# PCB.net
KiCad netlist of a schematic drawn in EAGLE
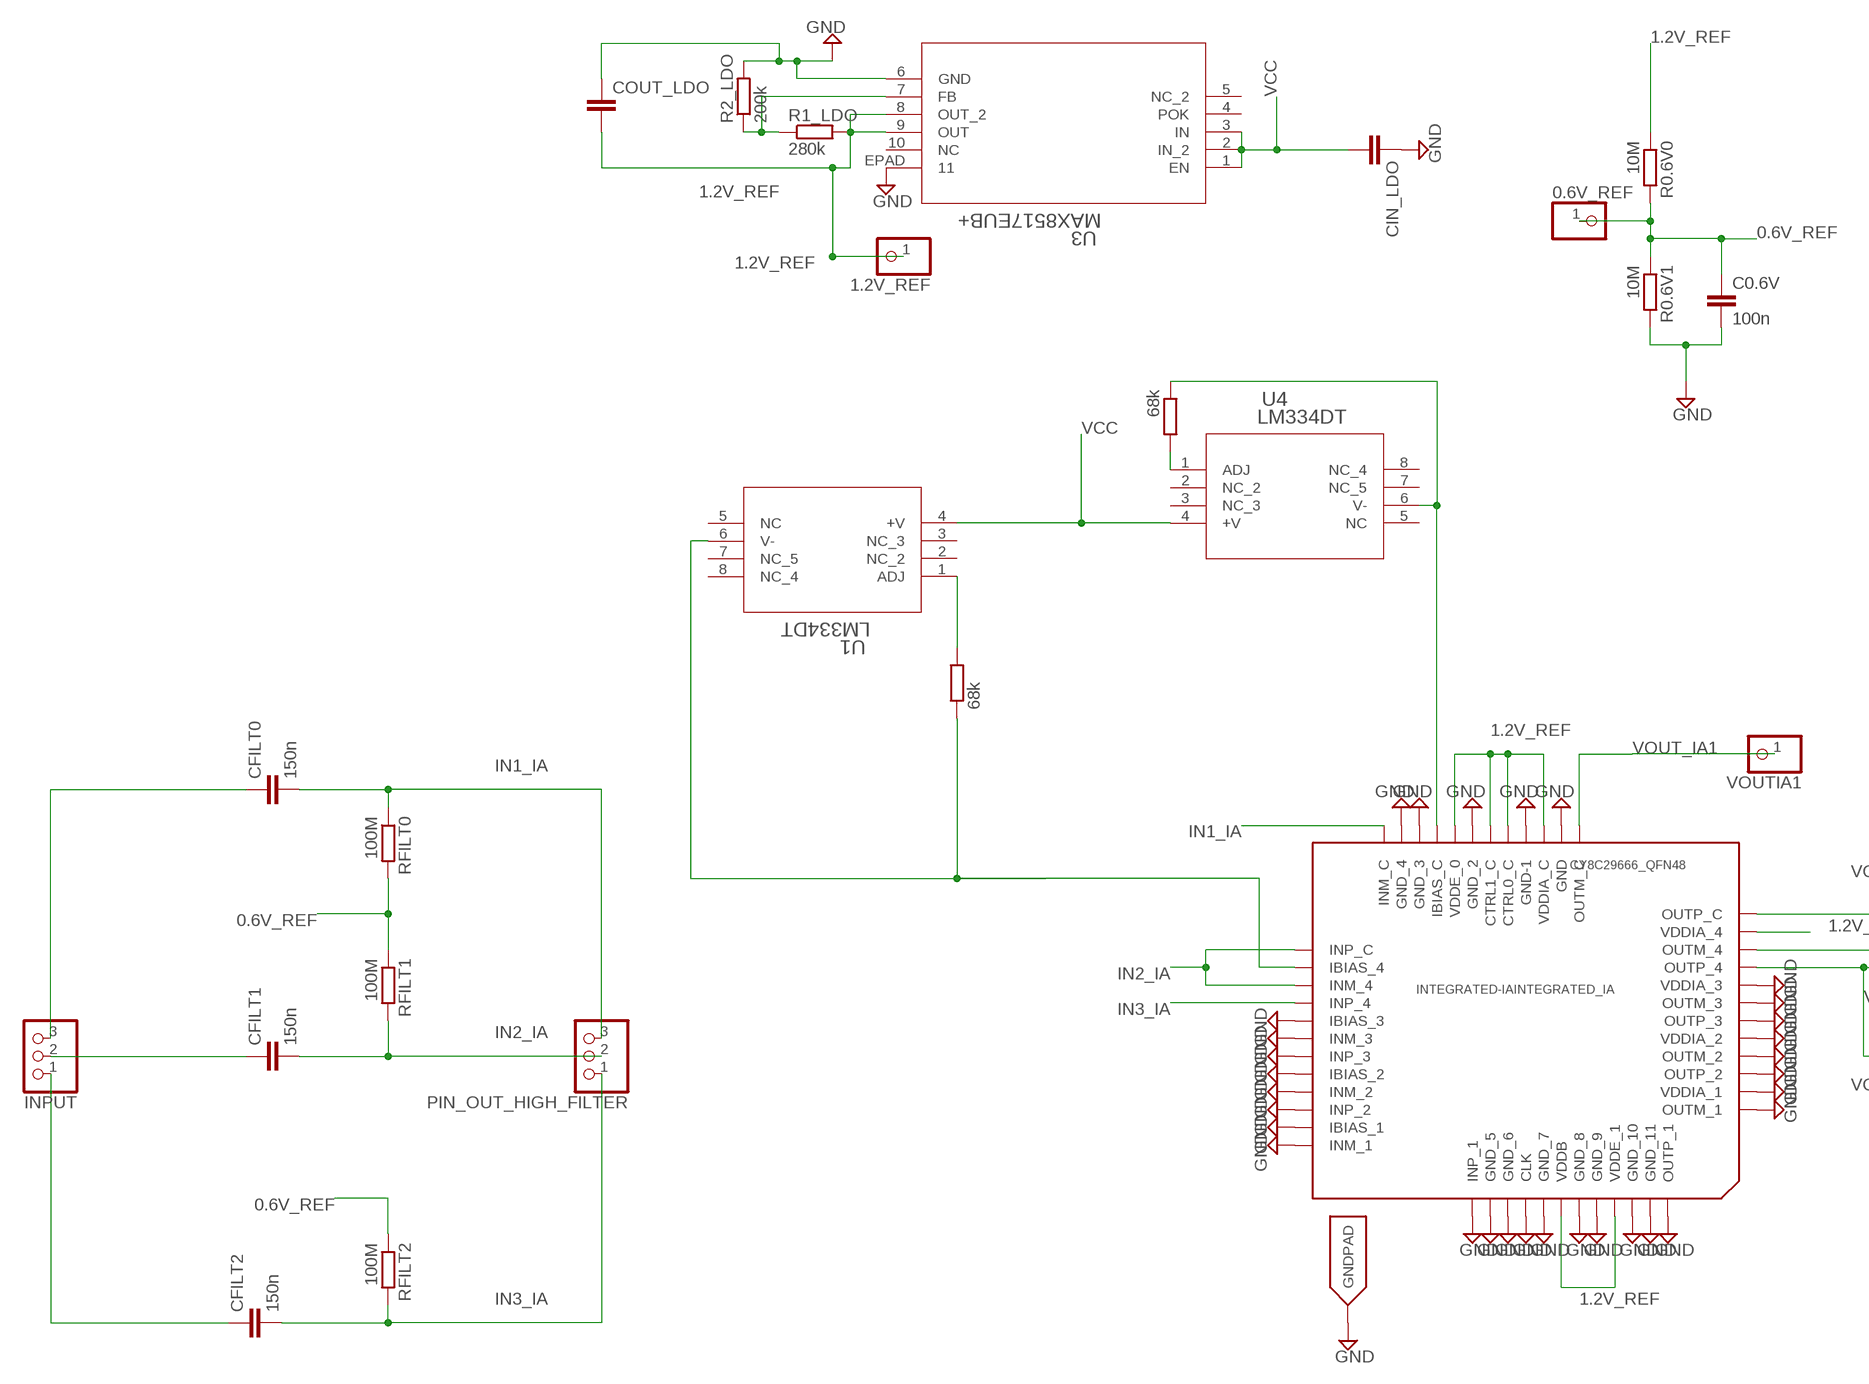
[diagram p0: schematic, sheet 1, part 1 of 2]
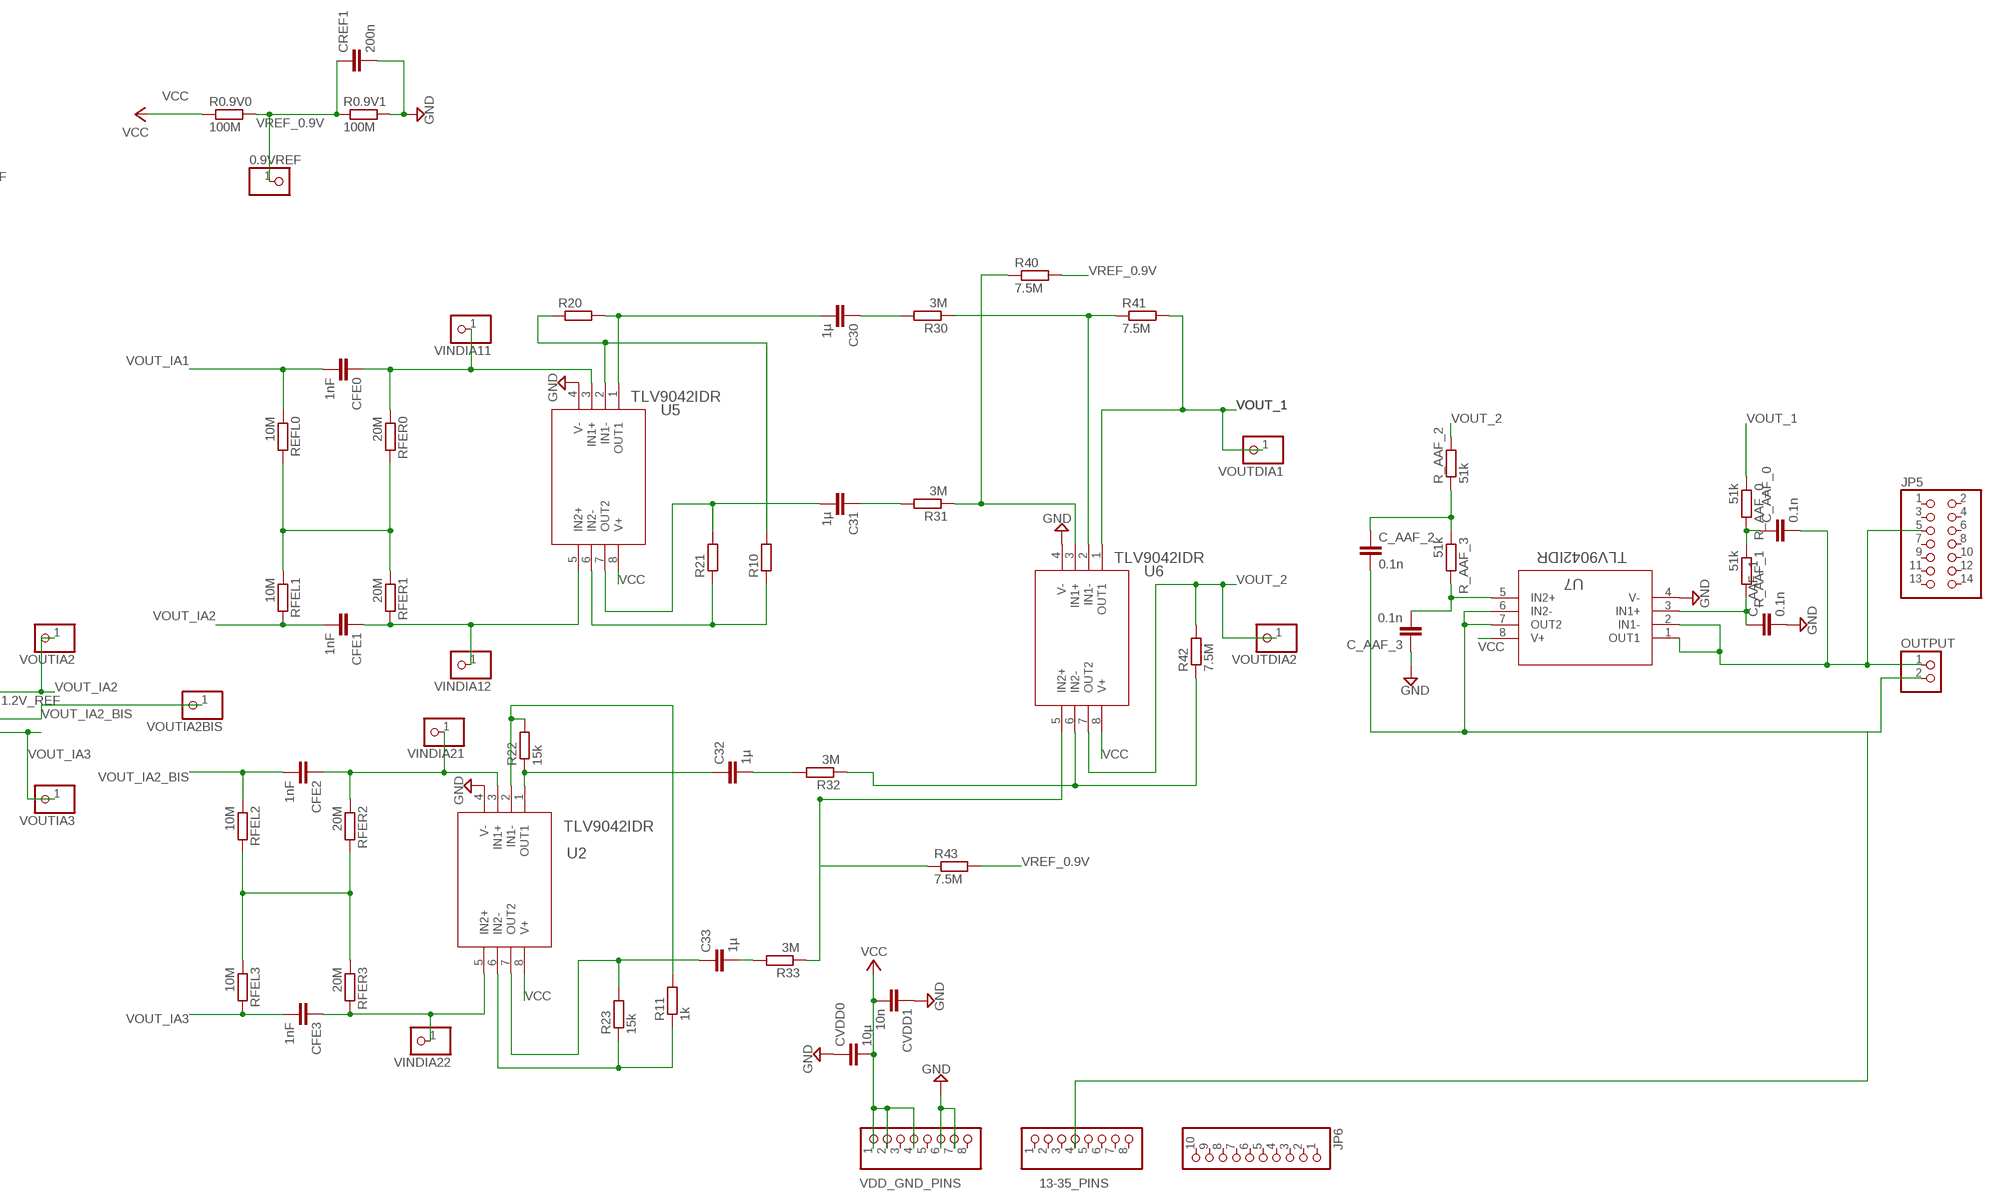
[diagram p1: schematic, sheet 1, part 2 of 2]

(export (version "E")
  (design (tool "Eeschema 10.0.6"))
  (components
    (comp (ref "0.6V_REF")
      (value "PINHD-1X1")
      (footprint "eagle-import:1X01")
      (libsource (lib "eagle-import") (part "PINHD-1X1"))
    )
    (comp (ref "0.9VREF")
      (value "PINHD-1X1")
      (footprint "eagle-import:1X01")
      (libsource (lib "eagle-import") (part "PINHD-1X1"))
    )
    (comp (ref "1.2V_REF")
      (value "PINHD-1X1")
      (footprint "eagle-import:1X01")
      (libsource (lib "eagle-import") (part "PINHD-1X1"))
    )
    (comp (ref "13-35_PINS")
      (value "PINHD-1X8")
      (footprint "eagle-import:1X08")
      (libsource (lib "eagle-import") (part "PINHD-1X8"))
    )
    (comp (ref "C0.6V")
      (value "100n")
      (footprint "eagle-import:C0603")
      (libsource (lib "eagle-import") (part "C-EUC0603"))
    )
    (comp (ref "C30")
      (value "1µ")
      (footprint "eagle-import:C0603")
      (libsource (lib "eagle-import") (part "C-EUC0603"))
    )
    (comp (ref "C31")
      (value "1µ")
      (footprint "eagle-import:C0603")
      (libsource (lib "eagle-import") (part "C-EUC0603"))
    )
    (comp (ref "C32")
      (value "1µ")
      (footprint "eagle-import:C0603")
      (libsource (lib "eagle-import") (part "C-EUC0603"))
    )
    (comp (ref "C33")
      (value "1µ")
      (footprint "eagle-import:C0603")
      (libsource (lib "eagle-import") (part "C-EUC0603"))
    )
    (comp (ref "CFE0")
      (value "1nF")
      (footprint "eagle-import:C0603")
      (libsource (lib "eagle-import") (part "C-EUC0603"))
    )
    (comp (ref "CFE1")
      (value "1nF")
      (footprint "eagle-import:C0603")
      (libsource (lib "eagle-import") (part "C-EUC0603"))
    )
    (comp (ref "CFE2")
      (value "1nF")
      (footprint "eagle-import:C0603")
      (libsource (lib "eagle-import") (part "C-EUC0603"))
    )
    (comp (ref "CFE3")
      (value "1nF")
      (footprint "eagle-import:C0603")
      (libsource (lib "eagle-import") (part "C-EUC0603"))
    )
    (comp (ref "CFILT0")
      (value "150n")
      (footprint "eagle-import:C0603")
      (libsource (lib "eagle-import") (part "C-EUC0603"))
    )
    (comp (ref "CFILT1")
      (value "150n")
      (footprint "eagle-import:C0603")
      (libsource (lib "eagle-import") (part "C-EUC0603"))
    )
    (comp (ref "CFILT2")
      (value "150n")
      (footprint "eagle-import:C0603")
      (libsource (lib "eagle-import") (part "C-EUC0603"))
    )
    (comp (ref "CIN_LDO")
      (value "1µ")
      (footprint "eagle-import:C0603")
      (libsource (lib "eagle-import") (part "C-EUC0603"))
    )
    (comp (ref "COUT_LDO")
      (value "4.7µ")
      (footprint "eagle-import:C0603")
      (libsource (lib "eagle-import") (part "C-EUC0603"))
    )
    (comp (ref "CREF1")
      (value "200n")
      (footprint "eagle-import:C0603")
      (libsource (lib "eagle-import") (part "C-EUC0603"))
    )
    (comp (ref "CVDD0")
      (value "10µ")
      (footprint "eagle-import:C0603")
      (libsource (lib "eagle-import") (part "C-EUC0603"))
    )
    (comp (ref "CVDD1")
      (value "10n")
      (footprint "eagle-import:C0603")
      (libsource (lib "eagle-import") (part "C-EUC0603"))
    )
    (comp (ref "C_AAF_0")
      (value "0.1n")
      (footprint "eagle-import:C0603")
      (libsource (lib "eagle-import") (part "C-EUC0603"))
    )
    (comp (ref "C_AAF_1")
      (value "0.1n")
      (footprint "eagle-import:C0603")
      (libsource (lib "eagle-import") (part "C-EUC0603"))
    )
    (comp (ref "C_AAF_2")
      (value "0.1n")
      (footprint "eagle-import:C0603")
      (libsource (lib "eagle-import") (part "C-EUC0603"))
    )
    (comp (ref "C_AAF_3")
      (value "0.1n")
      (footprint "eagle-import:C0603")
      (libsource (lib "eagle-import") (part "C-EUC0603"))
    )
    (comp (ref "INPUT")
      (value "PINHD-1X3")
      (footprint "eagle-import:1X03")
      (libsource (lib "eagle-import") (part "PINHD-1X3"))
    )
    (comp (ref "INTEGRATED-IA")
      (value "CY8C29666_QFN48")
      (footprint "eagle-import:QFN48")
      (libsource (lib "eagle-import") (part "CY8C29666_QFN48"))
    )
    (comp (ref "JP5")
      (value "PINHD-2X7")
      (footprint "eagle-import:2X07")
      (libsource (lib "eagle-import") (part "PINHD-2X7"))
    )
    (comp (ref "JP6")
      (value "PINHD-1X10")
      (footprint "eagle-import:1X10")
      (libsource (lib "eagle-import") (part "PINHD-1X10"))
    )
    (comp (ref "OUTPUT")
      (value "PINHD-1X2")
      (footprint "eagle-import:1X02")
      (libsource (lib "eagle-import") (part "PINHD-1X2"))
    )
    (comp (ref "PIN_OUT_HIGH_FILTER")
      (value "PINHD-1X3")
      (footprint "eagle-import:1X03")
      (libsource (lib "eagle-import") (part "PINHD-1X3"))
    )
    (comp (ref "R0.6V0")
      (value "10M")
      (footprint "eagle-import:R0603")
      (libsource (lib "eagle-import") (part "R-EU_R0603"))
    )
    (comp (ref "R0.6V1")
      (value "10M")
      (footprint "eagle-import:R0603")
      (libsource (lib "eagle-import") (part "R-EU_R0603"))
    )
    (comp (ref "R0.9V0")
      (value "100M")
      (footprint "eagle-import:R0603")
      (libsource (lib "eagle-import") (part "R-EU_R0603"))
    )
    (comp (ref "R0.9V1")
      (value "100M")
      (footprint "eagle-import:R0603")
      (libsource (lib "eagle-import") (part "R-EU_R0603"))
    )
    (comp (ref "R1_LDO")
      (value "280k")
      (footprint "eagle-import:R0603")
      (libsource (lib "eagle-import") (part "R-EU_R0603"))
    )
    (comp (ref "R2_LDO")
      (value "200k")
      (footprint "eagle-import:R0603")
      (libsource (lib "eagle-import") (part "R-EU_R0603"))
    )
    (comp (ref "R10")
      (value "R-EU_R0603")
      (footprint "eagle-import:R0603")
      (libsource (lib "eagle-import") (part "R-EU_R0603"))
    )
    (comp (ref "R11")
      (value "1k")
      (footprint "eagle-import:R0603")
      (libsource (lib "eagle-import") (part "R-EU_R0603"))
    )
    (comp (ref "R20")
      (value "R-EU_R0603")
      (footprint "eagle-import:R0603")
      (libsource (lib "eagle-import") (part "R-EU_R0603"))
    )
    (comp (ref "R21")
      (value "R-EU_R0603")
      (footprint "eagle-import:R0603")
      (libsource (lib "eagle-import") (part "R-EU_R0603"))
    )
    (comp (ref "R22")
      (value "15k")
      (footprint "eagle-import:R0603")
      (libsource (lib "eagle-import") (part "R-EU_R0603"))
    )
    (comp (ref "R23")
      (value "15k")
      (footprint "eagle-import:R0603")
      (libsource (lib "eagle-import") (part "R-EU_R0603"))
    )
    (comp (ref "R30")
      (value "3M")
      (footprint "eagle-import:R0603")
      (libsource (lib "eagle-import") (part "R-EU_R0603"))
    )
    (comp (ref "R31")
      (value "3M")
      (footprint "eagle-import:R0603")
      (libsource (lib "eagle-import") (part "R-EU_R0603"))
    )
    (comp (ref "R32")
      (value "3M")
      (footprint "eagle-import:R0603")
      (libsource (lib "eagle-import") (part "R-EU_R0603"))
    )
    (comp (ref "R33")
      (value "3M")
      (footprint "eagle-import:R0603")
      (libsource (lib "eagle-import") (part "R-EU_R0603"))
    )
    (comp (ref "R40")
      (value "7.5M")
      (footprint "eagle-import:R0603")
      (libsource (lib "eagle-import") (part "R-EU_R0603"))
    )
    (comp (ref "R41")
      (value "7.5M")
      (footprint "eagle-import:R0603")
      (libsource (lib "eagle-import") (part "R-EU_R0603"))
    )
    (comp (ref "R42")
      (value "7.5M")
      (footprint "eagle-import:R0603")
      (libsource (lib "eagle-import") (part "R-EU_R0603"))
    )
    (comp (ref "R43")
      (value "7.5M")
      (footprint "eagle-import:R0603")
      (libsource (lib "eagle-import") (part "R-EU_R0603"))
    )
    (comp (ref "REFL0")
      (value "10M")
      (footprint "eagle-import:R0603")
      (libsource (lib "eagle-import") (part "R-EU_R0603"))
    )
    (comp (ref "RFEL1")
      (value "10M")
      (footprint "eagle-import:R0603")
      (libsource (lib "eagle-import") (part "R-EU_R0603"))
    )
    (comp (ref "RFEL2")
      (value "10M")
      (footprint "eagle-import:R0603")
      (libsource (lib "eagle-import") (part "R-EU_R0603"))
    )
    (comp (ref "RFEL3")
      (value "10M")
      (footprint "eagle-import:R0603")
      (libsource (lib "eagle-import") (part "R-EU_R0603"))
    )
    (comp (ref "RFER0")
      (value "20M")
      (footprint "eagle-import:R0603")
      (libsource (lib "eagle-import") (part "R-EU_R0603"))
    )
    (comp (ref "RFER1")
      (value "20M")
      (footprint "eagle-import:R0603")
      (libsource (lib "eagle-import") (part "R-EU_R0603"))
    )
    (comp (ref "RFER2")
      (value "20M")
      (footprint "eagle-import:R0603")
      (libsource (lib "eagle-import") (part "R-EU_R0603"))
    )
    (comp (ref "RFER3")
      (value "20M")
      (footprint "eagle-import:R0603")
      (libsource (lib "eagle-import") (part "R-EU_R0603"))
    )
    (comp (ref "RFILT0")
      (value "100M")
      (footprint "eagle-import:R0603")
      (libsource (lib "eagle-import") (part "R-EU_R0603"))
    )
    (comp (ref "RFILT1")
      (value "100M")
      (footprint "eagle-import:R0603")
      (libsource (lib "eagle-import") (part "R-EU_R0603"))
    )
    (comp (ref "RFILT2")
      (value "100M")
      (footprint "eagle-import:R0603")
      (libsource (lib "eagle-import") (part "R-EU_R0603"))
    )
    (comp (ref "RLM334_0")
      (value "68k")
      (footprint "eagle-import:R0603")
      (libsource (lib "eagle-import") (part "R-EU_R0603"))
    )
    (comp (ref "RLM334_1")
      (value "68k")
      (footprint "eagle-import:R0603")
      (libsource (lib "eagle-import") (part "R-EU_R0603"))
    )
    (comp (ref "R_AAF_0")
      (value "51k")
      (footprint "eagle-import:R0603")
      (libsource (lib "eagle-import") (part "R-EU_R0603"))
    )
    (comp (ref "R_AAF_1")
      (value "51k")
      (footprint "eagle-import:R0603")
      (libsource (lib "eagle-import") (part "R-EU_R0603"))
    )
    (comp (ref "R_AAF_2")
      (value "51k")
      (footprint "eagle-import:R0603")
      (libsource (lib "eagle-import") (part "R-EU_R0603"))
    )
    (comp (ref "R_AAF_3")
      (value "51k")
      (footprint "eagle-import:R0603")
      (libsource (lib "eagle-import") (part "R-EU_R0603"))
    )
    (comp (ref "U1")
      (value "LM334DT")
      (footprint "eagle-import:SO-8_STM")
      (libsource (lib "eagle-import") (part "LM334DT"))
    )
    (comp (ref "U2")
      (value "TLV9042IDR")
      (footprint "eagle-import:SOIC8_D_TEX")
      (fields (field (name "COPYRIGHT") "Copyright (C) 2018 Accelerated Designs. All rights reserved"))
      (libsource (lib "eagle-import") (part "TLV9042IDR"))
    )
    (comp (ref "U3")
      (value "MAX8517EUB+")
      (footprint "eagle-import:21-0109D_MXM")
      (libsource (lib "eagle-import") (part "MAX8517EUB+"))
    )
    (comp (ref "U4")
      (value "LM334DT")
      (footprint "eagle-import:SO-8_STM")
      (libsource (lib "eagle-import") (part "LM334DT"))
    )
    (comp (ref "U5")
      (value "TLV9042IDR")
      (footprint "eagle-import:SOIC8_D_TEX")
      (fields (field (name "COPYRIGHT") "Copyright (C) 2018 Accelerated Designs. All rights reserved"))
      (libsource (lib "eagle-import") (part "TLV9042IDR"))
    )
    (comp (ref "U6")
      (value "TLV9042IDR")
      (footprint "eagle-import:SOIC8_D_TEX")
      (fields (field (name "COPYRIGHT") "Copyright (C) 2018 Accelerated Designs. All rights reserved"))
      (libsource (lib "eagle-import") (part "TLV9042IDR"))
    )
    (comp (ref "U7")
      (value "TLV9042IDR")
      (footprint "eagle-import:SOIC8_D_TEX")
      (fields (field (name "COPYRIGHT") "Copyright (C) 2018 Accelerated Designs. All rights reserved"))
      (libsource (lib "eagle-import") (part "TLV9042IDR"))
    )
    (comp (ref "VDD_GND_PINS")
      (value "PINHD-1X8")
      (footprint "eagle-import:1X08")
      (libsource (lib "eagle-import") (part "PINHD-1X8"))
    )
    (comp (ref "VINDIA11")
      (value "PINHD-1X1")
      (footprint "eagle-import:1X01")
      (libsource (lib "eagle-import") (part "PINHD-1X1"))
    )
    (comp (ref "VINDIA12")
      (value "PINHD-1X1")
      (footprint "eagle-import:1X01")
      (libsource (lib "eagle-import") (part "PINHD-1X1"))
    )
    (comp (ref "VINDIA21")
      (value "PINHD-1X1")
      (footprint "eagle-import:1X01")
      (libsource (lib "eagle-import") (part "PINHD-1X1"))
    )
    (comp (ref "VINDIA22")
      (value "PINHD-1X1")
      (footprint "eagle-import:1X01")
      (libsource (lib "eagle-import") (part "PINHD-1X1"))
    )
    (comp (ref "VOUTDIA1")
      (value "PINHD-1X1")
      (footprint "eagle-import:1X01")
      (libsource (lib "eagle-import") (part "PINHD-1X1"))
    )
    (comp (ref "VOUTDIA2")
      (value "PINHD-1X1")
      (footprint "eagle-import:1X01")
      (libsource (lib "eagle-import") (part "PINHD-1X1"))
    )
    (comp (ref "VOUTIA1")
      (value "PINHD-1X1")
      (footprint "eagle-import:1X01")
      (libsource (lib "eagle-import") (part "PINHD-1X1"))
    )
    (comp (ref "VOUTIA2")
      (value "PINHD-1X1")
      (footprint "eagle-import:1X01")
      (libsource (lib "eagle-import") (part "PINHD-1X1"))
    )
    (comp (ref "VOUTIA2BIS")
      (value "PINHD-1X1")
      (footprint "eagle-import:1X01")
      (libsource (lib "eagle-import") (part "PINHD-1X1"))
    )
    (comp (ref "VOUTIA3")
      (value "PINHD-1X1")
      (footprint "eagle-import:1X01")
      (libsource (lib "eagle-import") (part "PINHD-1X1"))
    )
  )
  (nets
    (net (code "1") (name "/0.6V_REF") (class "Default")
      (node (ref "0.6V_REF") (pin "1") (pinfunction "1_1") (pintype "passive"))
      (node (ref "C0.6V") (pin "1") (pinfunction "1_1") (pintype "passive"))
      (node (ref "R0.6V0") (pin "2") (pinfunction "2_2") (pintype "passive"))
      (node (ref "R0.6V1") (pin "1") (pinfunction "1_1") (pintype "passive"))
      (node (ref "RFILT0") (pin "2") (pinfunction "2_2") (pintype "passive"))
      (node (ref "RFILT1") (pin "1") (pinfunction "1_1") (pintype "passive"))
      (node (ref "RFILT2") (pin "1") (pinfunction "1_1") (pintype "passive"))
    )
    (net (code "2") (name "/1.2V_REF") (class "Default")
      (node (ref "1.2V_REF") (pin "1") (pinfunction "1_1") (pintype "passive"))
      (node (ref "COUT_LDO") (pin "2") (pinfunction "2_2") (pintype "passive"))
      (node (ref "INTEGRATED-IA") (pin "11") (pinfunction "VDDIA_4_11") (pintype "bidirectional"))
      (node (ref "INTEGRATED-IA") (pin "15") (pinfunction "VDDIA_C_15") (pintype "bidirectional"))
      (node (ref "INTEGRATED-IA") (pin "17") (pinfunction "CTRL0_C_17") (pintype "bidirectional"))
      (node (ref "INTEGRATED-IA") (pin "18") (pinfunction "CTRL1_C_18") (pintype "power_in"))
      (node (ref "INTEGRATED-IA") (pin "20") (pinfunction "VDDE_0_20") (pintype "bidirectional"))
      (node (ref "INTEGRATED-IA") (pin "42") (pinfunction "VDDB_42") (pintype "power_in"))
      (node (ref "INTEGRATED-IA") (pin "45") (pinfunction "VDDE_1_45") (pintype "bidirectional"))
      (node (ref "R0.6V0") (pin "1") (pinfunction "1_1") (pintype "passive"))
      (node (ref "R1_LDO") (pin "2") (pinfunction "2_2") (pintype "passive"))
      (node (ref "U3") (pin "8") (pinfunction "OUT_2_8") (pintype "output"))
      (node (ref "U3") (pin "9") (pinfunction "OUT_9") (pintype "output"))
    )
    (net (code "3") (name "/IN1_IA") (class "Default")
      (node (ref "CFILT0") (pin "2") (pinfunction "2_2") (pintype "passive"))
      (node (ref "INTEGRATED-IA") (pin "24") (pinfunction "INM_C_24") (pintype "bidirectional"))
      (node (ref "PIN_OUT_HIGH_FILTER") (pin "3") (pinfunction "3_3") (pintype "passive"))
      (node (ref "RFILT0") (pin "1") (pinfunction "1_1") (pintype "passive"))
    )
    (net (code "4") (name "/IN2_IA") (class "Default")
      (node (ref "CFILT1") (pin "2") (pinfunction "2_2") (pintype "passive"))
      (node (ref "INTEGRATED-IA") (pin "25") (pinfunction "INP_C_25") (pintype "bidirectional"))
      (node (ref "INTEGRATED-IA") (pin "27") (pinfunction "INM_4_27") (pintype "bidirectional"))
      (node (ref "PIN_OUT_HIGH_FILTER") (pin "2") (pinfunction "2_2") (pintype "passive"))
      (node (ref "RFILT1") (pin "2") (pinfunction "2_2") (pintype "passive"))
    )
    (net (code "5") (name "/IN3_IA") (class "Default")
      (node (ref "CFILT2") (pin "2") (pinfunction "2_2") (pintype "passive"))
      (node (ref "INTEGRATED-IA") (pin "28") (pinfunction "INP_4_28") (pintype "bidirectional"))
      (node (ref "PIN_OUT_HIGH_FILTER") (pin "1") (pinfunction "1_1") (pintype "passive"))
      (node (ref "RFILT2") (pin "2") (pinfunction "2_2") (pintype "passive"))
    )
    (net (code "6") (name "/VOUT_1") (class "Default")
      (node (ref "R41") (pin "2") (pinfunction "2_2") (pintype "passive"))
      (node (ref "R_AAF_0") (pin "1") (pinfunction "1_1") (pintype "passive"))
      (node (ref "U6") (pin "1") (pinfunction "OUT1_1") (pintype "output"))
      (node (ref "VOUTDIA1") (pin "1") (pinfunction "1_1") (pintype "passive"))
    )
    (net (code "7") (name "/VOUT_2") (class "Default")
      (node (ref "R42") (pin "2") (pinfunction "2_2") (pintype "passive"))
      (node (ref "R_AAF_2") (pin "2") (pinfunction "2_2") (pintype "passive"))
      (node (ref "U6") (pin "7") (pinfunction "OUT2_7") (pintype "output"))
      (node (ref "VOUTDIA2") (pin "1") (pinfunction "1_1") (pintype "passive"))
    )
    (net (code "8") (name "/VOUT_IA1") (class "Default")
      (node (ref "CFE0") (pin "2") (pinfunction "2_2") (pintype "passive"))
      (node (ref "INTEGRATED-IA") (pin "13") (pinfunction "OUTM_C_13") (pintype "bidirectional"))
      (node (ref "REFL0") (pin "1") (pinfunction "1_1") (pintype "passive"))
      (node (ref "VOUTIA1") (pin "1") (pinfunction "1_1") (pintype "passive"))
    )
    (net (code "9") (name "/VOUT_IA2") (class "Default")
      (node (ref "CFE1") (pin "2") (pinfunction "2_2") (pintype "passive"))
      (node (ref "INTEGRATED-IA") (pin "12") (pinfunction "OUTP_C_12") (pintype "bidirectional"))
      (node (ref "RFEL1") (pin "2") (pinfunction "2_2") (pintype "passive"))
      (node (ref "VOUTIA2") (pin "1") (pinfunction "1_1") (pintype "passive"))
    )
    (net (code "10") (name "/VOUT_IA2_BIS") (class "Default")
      (node (ref "CFE2") (pin "2") (pinfunction "2_2") (pintype "passive"))
      (node (ref "INTEGRATED-IA") (pin "10") (pinfunction "OUTM_4_10") (pintype "bidirectional"))
      (node (ref "RFEL2") (pin "1") (pinfunction "1_1") (pintype "passive"))
      (node (ref "VOUTIA2BIS") (pin "1") (pinfunction "1_1") (pintype "passive"))
    )
    (net (code "11") (name "/VOUT_IA3") (class "Default")
      (node (ref "CFE3") (pin "2") (pinfunction "2_2") (pintype "passive"))
      (node (ref "INTEGRATED-IA") (pin "9") (pinfunction "OUTP_4_9") (pintype "bidirectional"))
      (node (ref "RFEL3") (pin "2") (pinfunction "2_2") (pintype "passive"))
      (node (ref "VOUTIA3") (pin "1") (pinfunction "1_1") (pintype "passive"))
    )
    (net (code "12") (name "/VREF_0.9V") (class "Default")
      (node (ref "0.9VREF") (pin "1") (pinfunction "1_1") (pintype "passive"))
      (node (ref "CREF1") (pin "1") (pinfunction "1_1") (pintype "passive"))
      (node (ref "R0.9V0") (pin "2") (pinfunction "2_2") (pintype "passive"))
      (node (ref "R0.9V1") (pin "1") (pinfunction "1_1") (pintype "passive"))
      (node (ref "R40") (pin "2") (pinfunction "2_2") (pintype "passive"))
      (node (ref "R43") (pin "2") (pinfunction "2_2") (pintype "passive"))
    )
    (net (code "13") (name "GND") (class "Default")
      (node (ref "C0.6V") (pin "2") (pinfunction "2_2") (pintype "passive"))
      (node (ref "CIN_LDO") (pin "1") (pinfunction "1_1") (pintype "passive"))
      (node (ref "COUT_LDO") (pin "1") (pinfunction "1_1") (pintype "passive"))
      (node (ref "CREF1") (pin "2") (pinfunction "2_2") (pintype "passive"))
      (node (ref "CVDD0") (pin "1") (pinfunction "1_1") (pintype "passive"))
      (node (ref "CVDD1") (pin "1") (pinfunction "1_1") (pintype "passive"))
      (node (ref "C_AAF_1") (pin "2") (pinfunction "2_2") (pintype "passive"))
      (node (ref "C_AAF_3") (pin "1") (pinfunction "1_1") (pintype "passive"))
      (node (ref "INTEGRATED-IA") (pin "1") (pinfunction "OUTM_1_1") (pintype "bidirectional"))
      (node (ref "INTEGRATED-IA") (pin "14") (pinfunction "GND_14") (pintype "bidirectional"))
      (node (ref "INTEGRATED-IA") (pin "16") (pinfunction "GND-1_16") (pintype "bidirectional"))
      (node (ref "INTEGRATED-IA") (pin "19") (pinfunction "GND_2_19") (pintype "bidirectional"))
      (node (ref "INTEGRATED-IA") (pin "2") (pinfunction "VDDIA_1_2") (pintype "bidirectional"))
      (node (ref "INTEGRATED-IA") (pin "22") (pinfunction "GND_3_22") (pintype "bidirectional"))
      (node (ref "INTEGRATED-IA") (pin "23") (pinfunction "GND_4_23") (pintype "bidirectional"))
      (node (ref "INTEGRATED-IA") (pin "29") (pinfunction "IBIAS_3_29") (pintype "bidirectional"))
      (node (ref "INTEGRATED-IA") (pin "3") (pinfunction "OUTP_2_3") (pintype "bidirectional"))
      (node (ref "INTEGRATED-IA") (pin "30") (pinfunction "INM_3_30") (pintype "bidirectional"))
      (node (ref "INTEGRATED-IA") (pin "31") (pinfunction "INP_3_31") (pintype "bidirectional"))
      (node (ref "INTEGRATED-IA") (pin "32") (pinfunction "IBIAS_2_32") (pintype "bidirectional"))
      (node (ref "INTEGRATED-IA") (pin "33") (pinfunction "INM_2_33") (pintype "bidirectional"))
      (node (ref "INTEGRATED-IA") (pin "34") (pinfunction "INP_2_34") (pintype "bidirectional"))
      (node (ref "INTEGRATED-IA") (pin "35") (pinfunction "IBIAS_1_35") (pintype "bidirectional"))
      (node (ref "INTEGRATED-IA") (pin "36") (pinfunction "INM_1_36") (pintype "bidirectional"))
      (node (ref "INTEGRATED-IA") (pin "37") (pinfunction "INP_1_37") (pintype "bidirectional"))
      (node (ref "INTEGRATED-IA") (pin "38") (pinfunction "GND_5_38") (pintype "bidirectional"))
      (node (ref "INTEGRATED-IA") (pin "39") (pinfunction "GND_6_39") (pintype "bidirectional"))
      (node (ref "INTEGRATED-IA") (pin "4") (pinfunction "OUTM_2_4") (pintype "bidirectional"))
      (node (ref "INTEGRATED-IA") (pin "40") (pinfunction "CLK_40") (pintype "bidirectional"))
      (node (ref "INTEGRATED-IA") (pin "41") (pinfunction "GND_7_41") (pintype "bidirectional"))
      (node (ref "INTEGRATED-IA") (pin "43") (pinfunction "GND_8_43") (pintype "bidirectional"))
      (node (ref "INTEGRATED-IA") (pin "44") (pinfunction "GND_9_44") (pintype "bidirectional"))
      (node (ref "INTEGRATED-IA") (pin "46") (pinfunction "GND_10_46") (pintype "bidirectional"))
      (node (ref "INTEGRATED-IA") (pin "47") (pinfunction "GND_11_47") (pintype "bidirectional"))
      (node (ref "INTEGRATED-IA") (pin "48") (pinfunction "OUTP_1_48") (pintype "bidirectional"))
      (node (ref "INTEGRATED-IA") (pin "5") (pinfunction "VDDIA_2_5") (pintype "bidirectional"))
      (node (ref "INTEGRATED-IA") (pin "6") (pinfunction "OUTP_3_6") (pintype "bidirectional"))
      (node (ref "INTEGRATED-IA") (pin "7") (pinfunction "OUTM_3_7") (pintype "power_in"))
      (node (ref "INTEGRATED-IA") (pin "8") (pinfunction "VDDIA_3_8") (pintype "bidirectional"))
      (node (ref "INTEGRATED-IA") (pin "EXP") (pinfunction "GNDPAD_EXP") (pintype "power_in"))
      (node (ref "R0.6V1") (pin "2") (pinfunction "2_2") (pintype "passive"))
      (node (ref "R0.9V1") (pin "2") (pinfunction "2_2") (pintype "passive"))
      (node (ref "R2_LDO") (pin "2") (pinfunction "2_2") (pintype "passive"))
      (node (ref "U2") (pin "4") (pinfunction "V-_4") (pintype "power_in"))
      (node (ref "U3") (pin "6") (pinfunction "GND_6") (pintype "power_in"))
      (node (ref "U3") (pin "EPAD") (pinfunction "11_EPAD") (pintype "passive"))
      (node (ref "U5") (pin "4") (pinfunction "V-_4") (pintype "power_in"))
      (node (ref "U6") (pin "4") (pinfunction "V-_4") (pintype "power_in"))
      (node (ref "U7") (pin "4") (pinfunction "V-_4") (pintype "power_in"))
      (node (ref "VDD_GND_PINS") (pin "6") (pinfunction "6_6") (pintype "passive"))
      (node (ref "VDD_GND_PINS") (pin "7") (pinfunction "7_7") (pintype "passive"))
    )
    (net (code "14") (name "Net-(C30-Pad1)") (class "Default")
      (node (ref "C30") (pin "1") (pinfunction "1_1") (pintype "passive"))
      (node (ref "R30") (pin "2") (pinfunction "2_2") (pintype "passive"))
    )
    (net (code "15") (name "Net-(C31-Pad1)") (class "Default")
      (node (ref "C31") (pin "1") (pinfunction "1_1") (pintype "passive"))
      (node (ref "R31") (pin "2") (pinfunction "2_2") (pintype "passive"))
    )
    (net (code "16") (name "Net-(C32-Pad2)") (class "Default")
      (node (ref "C32") (pin "2") (pinfunction "2_2") (pintype "passive"))
      (node (ref "R32") (pin "2") (pinfunction "2_2") (pintype "passive"))
    )
    (net (code "17") (name "Net-(C33-Pad2)") (class "Default")
      (node (ref "C33") (pin "2") (pinfunction "2_2") (pintype "passive"))
      (node (ref "R33") (pin "2") (pinfunction "2_2") (pintype "passive"))
    )
    (net (code "18") (name "Net-(CFILT0-Pad1)") (class "Default")
      (node (ref "CFILT0") (pin "1") (pinfunction "1_1") (pintype "passive"))
      (node (ref "INPUT") (pin "3") (pinfunction "3_3") (pintype "passive"))
    )
    (net (code "19") (name "Net-(CFILT1-Pad1)") (class "Default")
      (node (ref "CFILT1") (pin "1") (pinfunction "1_1") (pintype "passive"))
      (node (ref "INPUT") (pin "2") (pinfunction "2_2") (pintype "passive"))
    )
    (net (code "20") (name "Net-(CFILT2-Pad1)") (class "Default")
      (node (ref "CFILT2") (pin "1") (pinfunction "1_1") (pintype "passive"))
      (node (ref "INPUT") (pin "1") (pinfunction "1_1") (pintype "passive"))
    )
    (net (code "21") (name "Net-(C_AAF_0-Pad1)") (class "Default")
      (node (ref "C_AAF_0") (pin "1") (pinfunction "1_1") (pintype "passive"))
      (node (ref "R_AAF_0") (pin "2") (pinfunction "2_2") (pintype "passive"))
      (node (ref "R_AAF_1") (pin "1") (pinfunction "1_1") (pintype "passive"))
    )
    (net (code "22") (name "Net-(C_AAF_2-Pad1)") (class "Default")
      (node (ref "C_AAF_2") (pin "1") (pinfunction "1_1") (pintype "passive"))
      (node (ref "R_AAF_2") (pin "1") (pinfunction "1_1") (pintype "passive"))
      (node (ref "R_AAF_3") (pin "1") (pinfunction "1_1") (pintype "passive"))
    )
    (net (code "23") (name "Net-(INTEGRATED-IAB-IBIAS_4)") (class "Default")
      (node (ref "INTEGRATED-IA") (pin "26") (pinfunction "IBIAS_4_26") (pintype "bidirectional"))
      (node (ref "RLM334_1") (pin "1") (pinfunction "1_1") (pintype "passive"))
      (node (ref "U1") (pin "6") (pinfunction "V-_6") (pintype "power_in"))
    )
    (net (code "24") (name "Net-(INTEGRATED-IAB-IBIAS_C)") (class "Default")
      (node (ref "INTEGRATED-IA") (pin "21") (pinfunction "IBIAS_C_21") (pintype "bidirectional"))
      (node (ref "RLM334_0") (pin "1") (pinfunction "1_1") (pintype "passive"))
      (node (ref "U4") (pin "6") (pinfunction "V-_6") (pintype "power_in"))
    )
    (net (code "25") (name "Net-(REFL0-Pad2)") (class "Default")
      (node (ref "REFL0") (pin "2") (pinfunction "2_2") (pintype "passive"))
      (node (ref "RFEL1") (pin "1") (pinfunction "1_1") (pintype "passive"))
      (node (ref "RFER0") (pin "2") (pinfunction "2_2") (pintype "passive"))
      (node (ref "RFER1") (pin "1") (pinfunction "1_1") (pintype "passive"))
    )
    (net (code "26") (name "Net-(RFEL2-Pad2)") (class "Default")
      (node (ref "RFEL2") (pin "2") (pinfunction "2_2") (pintype "passive"))
      (node (ref "RFEL3") (pin "1") (pinfunction "1_1") (pintype "passive"))
      (node (ref "RFER2") (pin "2") (pinfunction "2_2") (pintype "passive"))
      (node (ref "RFER3") (pin "1") (pinfunction "1_1") (pintype "passive"))
    )
    (net (code "27") (name "Net-(U1-ADJ)") (class "Default")
      (node (ref "RLM334_1") (pin "2") (pinfunction "2_2") (pintype "passive"))
      (node (ref "U1") (pin "1") (pinfunction "ADJ_1") (pintype "input"))
    )
    (net (code "28") (name "Net-(U2-IN1+)") (class "Default")
      (node (ref "CFE2") (pin "1") (pinfunction "1_1") (pintype "passive"))
      (node (ref "RFER2") (pin "1") (pinfunction "1_1") (pintype "passive"))
      (node (ref "U2") (pin "3") (pinfunction "IN1+_3") (pintype "input"))
      (node (ref "VINDIA21") (pin "1") (pinfunction "1_1") (pintype "passive"))
    )
    (net (code "29") (name "Net-(U2-IN1-)") (class "Default")
      (node (ref "R11") (pin "2") (pinfunction "2_2") (pintype "passive"))
      (node (ref "R22") (pin "2") (pinfunction "2_2") (pintype "passive"))
      (node (ref "U2") (pin "2") (pinfunction "IN1-_2") (pintype "input"))
    )
    (net (code "30") (name "Net-(U2-IN2+)") (class "Default")
      (node (ref "CFE3") (pin "1") (pinfunction "1_1") (pintype "passive"))
      (node (ref "RFER3") (pin "2") (pinfunction "2_2") (pintype "passive"))
      (node (ref "U2") (pin "5") (pinfunction "IN2+_5") (pintype "input"))
      (node (ref "VINDIA22") (pin "1") (pinfunction "1_1") (pintype "passive"))
    )
    (net (code "31") (name "Net-(U2-IN2-)") (class "Default")
      (node (ref "R11") (pin "1") (pinfunction "1_1") (pintype "passive"))
      (node (ref "R23") (pin "1") (pinfunction "1_1") (pintype "passive"))
      (node (ref "U2") (pin "6") (pinfunction "IN2-_6") (pintype "input"))
    )
    (net (code "32") (name "Net-(U2-OUT1)") (class "Default")
      (node (ref "C32") (pin "1") (pinfunction "1_1") (pintype "passive"))
      (node (ref "R22") (pin "1") (pinfunction "1_1") (pintype "passive"))
      (node (ref "U2") (pin "1") (pinfunction "OUT1_1") (pintype "output"))
    )
    (net (code "33") (name "Net-(U2-OUT2)") (class "Default")
      (node (ref "C33") (pin "1") (pinfunction "1_1") (pintype "passive"))
      (node (ref "R23") (pin "2") (pinfunction "2_2") (pintype "passive"))
      (node (ref "U2") (pin "7") (pinfunction "OUT2_7") (pintype "output"))
    )
    (net (code "34") (name "Net-(U3-FB)") (class "Default")
      (node (ref "R1_LDO") (pin "1") (pinfunction "1_1") (pintype "passive"))
      (node (ref "R2_LDO") (pin "1") (pinfunction "1_1") (pintype "passive"))
      (node (ref "U3") (pin "7") (pinfunction "FB_7") (pintype "passive"))
    )
    (net (code "35") (name "Net-(U4-ADJ)") (class "Default")
      (node (ref "RLM334_0") (pin "2") (pinfunction "2_2") (pintype "passive"))
      (node (ref "U4") (pin "1") (pinfunction "ADJ_1") (pintype "input"))
    )
    (net (code "36") (name "Net-(U5-IN1+)") (class "Default")
      (node (ref "CFE0") (pin "1") (pinfunction "1_1") (pintype "passive"))
      (node (ref "RFER0") (pin "1") (pinfunction "1_1") (pintype "passive"))
      (node (ref "U5") (pin "3") (pinfunction "IN1+_3") (pintype "input"))
      (node (ref "VINDIA11") (pin "1") (pinfunction "1_1") (pintype "passive"))
    )
    (net (code "37") (name "Net-(U5-IN1-)") (class "Default")
      (node (ref "R10") (pin "2") (pinfunction "2_2") (pintype "passive"))
      (node (ref "R20") (pin "1") (pinfunction "1_1") (pintype "passive"))
      (node (ref "U5") (pin "2") (pinfunction "IN1-_2") (pintype "input"))
    )
    (net (code "38") (name "Net-(U5-IN2+)") (class "Default")
      (node (ref "CFE1") (pin "1") (pinfunction "1_1") (pintype "passive"))
      (node (ref "RFER1") (pin "2") (pinfunction "2_2") (pintype "passive"))
      (node (ref "U5") (pin "5") (pinfunction "IN2+_5") (pintype "input"))
      (node (ref "VINDIA12") (pin "1") (pinfunction "1_1") (pintype "passive"))
    )
    (net (code "39") (name "Net-(U5-IN2-)") (class "Default")
      (node (ref "R10") (pin "1") (pinfunction "1_1") (pintype "passive"))
      (node (ref "R21") (pin "1") (pinfunction "1_1") (pintype "passive"))
      (node (ref "U5") (pin "6") (pinfunction "IN2-_6") (pintype "input"))
    )
    (net (code "40") (name "Net-(U5-OUT1)") (class "Default")
      (node (ref "C30") (pin "2") (pinfunction "2_2") (pintype "passive"))
      (node (ref "R20") (pin "2") (pinfunction "2_2") (pintype "passive"))
      (node (ref "U5") (pin "1") (pinfunction "OUT1_1") (pintype "output"))
    )
    (net (code "41") (name "Net-(U5-OUT2)") (class "Default")
      (node (ref "C31") (pin "2") (pinfunction "2_2") (pintype "passive"))
      (node (ref "R21") (pin "2") (pinfunction "2_2") (pintype "passive"))
      (node (ref "U5") (pin "7") (pinfunction "OUT2_7") (pintype "output"))
    )
    (net (code "42") (name "Net-(U6-IN1+)") (class "Default")
      (node (ref "R31") (pin "1") (pinfunction "1_1") (pintype "passive"))
      (node (ref "R40") (pin "1") (pinfunction "1_1") (pintype "passive"))
      (node (ref "U6") (pin "3") (pinfunction "IN1+_3") (pintype "input"))
    )
    (net (code "43") (name "Net-(U6-IN1-)") (class "Default")
      (node (ref "R30") (pin "1") (pinfunction "1_1") (pintype "passive"))
      (node (ref "R41") (pin "1") (pinfunction "1_1") (pintype "passive"))
      (node (ref "U6") (pin "2") (pinfunction "IN1-_2") (pintype "input"))
    )
    (net (code "44") (name "Net-(U6-IN2+)") (class "Default")
      (node (ref "R33") (pin "1") (pinfunction "1_1") (pintype "passive"))
      (node (ref "R43") (pin "1") (pinfunction "1_1") (pintype "passive"))
      (node (ref "U6") (pin "5") (pinfunction "IN2+_5") (pintype "input"))
    )
    (net (code "45") (name "Net-(U6-IN2-)") (class "Default")
      (node (ref "R32") (pin "1") (pinfunction "1_1") (pintype "passive"))
      (node (ref "R42") (pin "1") (pinfunction "1_1") (pintype "passive"))
      (node (ref "U6") (pin "6") (pinfunction "IN2-_6") (pintype "input"))
    )
    (net (code "46") (name "Net-(U7-IN1+)") (class "Default")
      (node (ref "C_AAF_1") (pin "1") (pinfunction "1_1") (pintype "passive"))
      (node (ref "R_AAF_1") (pin "2") (pinfunction "2_2") (pintype "passive"))
      (node (ref "U7") (pin "3") (pinfunction "IN1+_3") (pintype "input"))
    )
    (net (code "47") (name "Net-(U7-IN1-)") (class "Default")
      (node (ref "C_AAF_0") (pin "2") (pinfunction "2_2") (pintype "passive"))
      (node (ref "JP5") (pin "5") (pinfunction "5_5") (pintype "passive"))
      (node (ref "OUTPUT") (pin "1") (pinfunction "1_1") (pintype "passive"))
      (node (ref "U7") (pin "1") (pinfunction "OUT1_1") (pintype "output"))
      (node (ref "U7") (pin "2") (pinfunction "IN1-_2") (pintype "input"))
    )
    (net (code "48") (name "Net-(U7-IN2+)") (class "Default")
      (node (ref "C_AAF_3") (pin "2") (pinfunction "2_2") (pintype "passive"))
      (node (ref "R_AAF_3") (pin "2") (pinfunction "2_2") (pintype "passive"))
      (node (ref "U7") (pin "5") (pinfunction "IN2+_5") (pintype "input"))
    )
    (net (code "49") (name "Net-(U7-IN2-)") (class "Default")
      (node (ref "13-35_PINS") (pin "4") (pinfunction "4_4") (pintype "passive"))
      (node (ref "C_AAF_2") (pin "2") (pinfunction "2_2") (pintype "passive"))
      (node (ref "OUTPUT") (pin "2") (pinfunction "2_2") (pintype "passive"))
      (node (ref "U7") (pin "6") (pinfunction "IN2-_6") (pintype "input"))
      (node (ref "U7") (pin "7") (pinfunction "OUT2_7") (pintype "output"))
    )
    (net (code "50") (name "VCC") (class "Default")
      (node (ref "CIN_LDO") (pin "2") (pinfunction "2_2") (pintype "passive"))
      (node (ref "CVDD0") (pin "2") (pinfunction "2_2") (pintype "passive"))
      (node (ref "CVDD1") (pin "2") (pinfunction "2_2") (pintype "passive"))
      (node (ref "R0.9V0") (pin "1") (pinfunction "1_1") (pintype "passive"))
      (node (ref "U1") (pin "4") (pinfunction "+V_4") (pintype "power_in"))
      (node (ref "U2") (pin "8") (pinfunction "V+_8") (pintype "power_in"))
      (node (ref "U3") (pin "1") (pinfunction "EN_1") (pintype "input"))
      (node (ref "U3") (pin "2") (pinfunction "IN_2_2") (pintype "input"))
      (node (ref "U3") (pin "3") (pinfunction "IN_3") (pintype "input"))
      (node (ref "U4") (pin "4") (pinfunction "+V_4") (pintype "power_in"))
      (node (ref "U5") (pin "8") (pinfunction "V+_8") (pintype "power_in"))
      (node (ref "U6") (pin "8") (pinfunction "V+_8") (pintype "power_in"))
      (node (ref "U7") (pin "8") (pinfunction "V+_8") (pintype "power_in"))
      (node (ref "VDD_GND_PINS") (pin "1") (pinfunction "1_1") (pintype "passive"))
      (node (ref "VDD_GND_PINS") (pin "2") (pinfunction "2_2") (pintype "passive"))
      (node (ref "VDD_GND_PINS") (pin "4") (pinfunction "4_4") (pintype "passive"))
    )
    (net (code "51") (name "unconnected-(13-35_PINS-Pad1)") (class "Default")
      (node (ref "13-35_PINS") (pin "1") (pinfunction "1_1") (pintype "passive"))
    )
    (net (code "52") (name "unconnected-(13-35_PINS-Pad2)") (class "Default")
      (node (ref "13-35_PINS") (pin "2") (pinfunction "2_2") (pintype "passive"))
    )
    (net (code "53") (name "unconnected-(13-35_PINS-Pad3)") (class "Default")
      (node (ref "13-35_PINS") (pin "3") (pinfunction "3_3") (pintype "passive"))
    )
    (net (code "54") (name "unconnected-(13-35_PINS-Pad5)") (class "Default")
      (node (ref "13-35_PINS") (pin "5") (pinfunction "5_5") (pintype "passive"))
    )
    (net (code "55") (name "unconnected-(13-35_PINS-Pad6)") (class "Default")
      (node (ref "13-35_PINS") (pin "6") (pinfunction "6_6") (pintype "passive"))
    )
    (net (code "56") (name "unconnected-(13-35_PINS-Pad7)") (class "Default")
      (node (ref "13-35_PINS") (pin "7") (pinfunction "7_7") (pintype "passive"))
    )
    (net (code "57") (name "unconnected-(13-35_PINS-Pad8)") (class "Default")
      (node (ref "13-35_PINS") (pin "8") (pinfunction "8_8") (pintype "passive"))
    )
    (net (code "58") (name "unconnected-(JP5-Pad1)") (class "Default")
      (node (ref "JP5") (pin "1") (pinfunction "1_1") (pintype "passive"))
    )
    (net (code "59") (name "unconnected-(JP5-Pad2)") (class "Default")
      (node (ref "JP5") (pin "2") (pinfunction "2_2") (pintype "passive"))
    )
    (net (code "60") (name "unconnected-(JP5-Pad3)") (class "Default")
      (node (ref "JP5") (pin "3") (pinfunction "3_3") (pintype "passive"))
    )
    (net (code "61") (name "unconnected-(JP5-Pad4)") (class "Default")
      (node (ref "JP5") (pin "4") (pinfunction "4_4") (pintype "passive"))
    )
    (net (code "62") (name "unconnected-(JP5-Pad6)") (class "Default")
      (node (ref "JP5") (pin "6") (pinfunction "6_6") (pintype "passive"))
    )
    (net (code "63") (name "unconnected-(JP5-Pad7)") (class "Default")
      (node (ref "JP5") (pin "7") (pinfunction "7_7") (pintype "passive"))
    )
    (net (code "64") (name "unconnected-(JP5-Pad8)") (class "Default")
      (node (ref "JP5") (pin "8") (pinfunction "8_8") (pintype "passive"))
    )
    (net (code "65") (name "unconnected-(JP5-Pad9)") (class "Default")
      (node (ref "JP5") (pin "9") (pinfunction "9_9") (pintype "passive"))
    )
    (net (code "66") (name "unconnected-(JP5-Pad10)") (class "Default")
      (node (ref "JP5") (pin "10") (pinfunction "10_10") (pintype "passive"))
    )
    (net (code "67") (name "unconnected-(JP5-Pad11)") (class "Default")
      (node (ref "JP5") (pin "11") (pinfunction "11_11") (pintype "passive"))
    )
    (net (code "68") (name "unconnected-(JP5-Pad12)") (class "Default")
      (node (ref "JP5") (pin "12") (pinfunction "12_12") (pintype "passive"))
    )
    (net (code "69") (name "unconnected-(JP5-Pad13)") (class "Default")
      (node (ref "JP5") (pin "13") (pinfunction "13_13") (pintype "passive"))
    )
    (net (code "70") (name "unconnected-(JP5-Pad14)") (class "Default")
      (node (ref "JP5") (pin "14") (pinfunction "14_14") (pintype "passive"))
    )
    (net (code "71") (name "unconnected-(JP6-Pad1)") (class "Default")
      (node (ref "JP6") (pin "1") (pinfunction "1_1") (pintype "passive"))
    )
    (net (code "72") (name "unconnected-(JP6-Pad2)") (class "Default")
      (node (ref "JP6") (pin "2") (pinfunction "2_2") (pintype "passive"))
    )
    (net (code "73") (name "unconnected-(JP6-Pad3)") (class "Default")
      (node (ref "JP6") (pin "3") (pinfunction "3_3") (pintype "passive"))
    )
    (net (code "74") (name "unconnected-(JP6-Pad4)") (class "Default")
      (node (ref "JP6") (pin "4") (pinfunction "4_4") (pintype "passive"))
    )
    (net (code "75") (name "unconnected-(JP6-Pad5)") (class "Default")
      (node (ref "JP6") (pin "5") (pinfunction "5_5") (pintype "passive"))
    )
    (net (code "76") (name "unconnected-(JP6-Pad6)") (class "Default")
      (node (ref "JP6") (pin "6") (pinfunction "6_6") (pintype "passive"))
    )
    (net (code "77") (name "unconnected-(JP6-Pad7)") (class "Default")
      (node (ref "JP6") (pin "7") (pinfunction "7_7") (pintype "passive"))
    )
    (net (code "78") (name "unconnected-(JP6-Pad8)") (class "Default")
      (node (ref "JP6") (pin "8") (pinfunction "8_8") (pintype "passive"))
    )
    (net (code "79") (name "unconnected-(JP6-Pad9)") (class "Default")
      (node (ref "JP6") (pin "9") (pinfunction "9_9") (pintype "passive"))
    )
    (net (code "80") (name "unconnected-(JP6-Pad10)") (class "Default")
      (node (ref "JP6") (pin "10") (pinfunction "10_10") (pintype "passive"))
    )
    (net (code "81") (name "unconnected-(U1-NC-Pad5)") (class "Default")
      (node (ref "U1") (pin "5") (pinfunction "NC_5") (pintype "no_connect"))
    )
    (net (code "82") (name "unconnected-(U1-NC_2-Pad2)") (class "Default")
      (node (ref "U1") (pin "2") (pinfunction "NC_2_2") (pintype "no_connect"))
    )
    (net (code "83") (name "unconnected-(U1-NC_3-Pad3)") (class "Default")
      (node (ref "U1") (pin "3") (pinfunction "NC_3_3") (pintype "no_connect"))
    )
    (net (code "84") (name "unconnected-(U1-NC_4-Pad8)") (class "Default")
      (node (ref "U1") (pin "8") (pinfunction "NC_4_8") (pintype "no_connect"))
    )
    (net (code "85") (name "unconnected-(U1-NC_5-Pad7)") (class "Default")
      (node (ref "U1") (pin "7") (pinfunction "NC_5_7") (pintype "no_connect"))
    )
    (net (code "86") (name "unconnected-(U3-NC-Pad10)") (class "Default")
      (node (ref "U3") (pin "10") (pinfunction "NC_10") (pintype "no_connect"))
    )
    (net (code "87") (name "unconnected-(U3-NC_2-Pad5)") (class "Default")
      (node (ref "U3") (pin "5") (pinfunction "NC_2_5") (pintype "no_connect"))
    )
    (net (code "88") (name "unconnected-(U3-POK-Pad4)") (class "Default")
      (node (ref "U3") (pin "4") (pinfunction "POK_4") (pintype "output"))
    )
    (net (code "89") (name "unconnected-(U4-NC-Pad5)") (class "Default")
      (node (ref "U4") (pin "5") (pinfunction "NC_5") (pintype "no_connect"))
    )
    (net (code "90") (name "unconnected-(U4-NC_2-Pad2)") (class "Default")
      (node (ref "U4") (pin "2") (pinfunction "NC_2_2") (pintype "no_connect"))
    )
    (net (code "91") (name "unconnected-(U4-NC_3-Pad3)") (class "Default")
      (node (ref "U4") (pin "3") (pinfunction "NC_3_3") (pintype "no_connect"))
    )
    (net (code "92") (name "unconnected-(U4-NC_4-Pad8)") (class "Default")
      (node (ref "U4") (pin "8") (pinfunction "NC_4_8") (pintype "no_connect"))
    )
    (net (code "93") (name "unconnected-(U4-NC_5-Pad7)") (class "Default")
      (node (ref "U4") (pin "7") (pinfunction "NC_5_7") (pintype "no_connect"))
    )
    (net (code "94") (name "unconnected-(VDD_GND_PINS-Pad3)") (class "Default")
      (node (ref "VDD_GND_PINS") (pin "3") (pinfunction "3_3") (pintype "passive"))
    )
    (net (code "95") (name "unconnected-(VDD_GND_PINS-Pad5)") (class "Default")
      (node (ref "VDD_GND_PINS") (pin "5") (pinfunction "5_5") (pintype "passive"))
    )
    (net (code "96") (name "unconnected-(VDD_GND_PINS-Pad8)") (class "Default")
      (node (ref "VDD_GND_PINS") (pin "8") (pinfunction "8_8") (pintype "passive"))
    )
  )
)
